# aqicluster_easyeda.net
KiCad netlist of a schematic drawn in EasyEDA
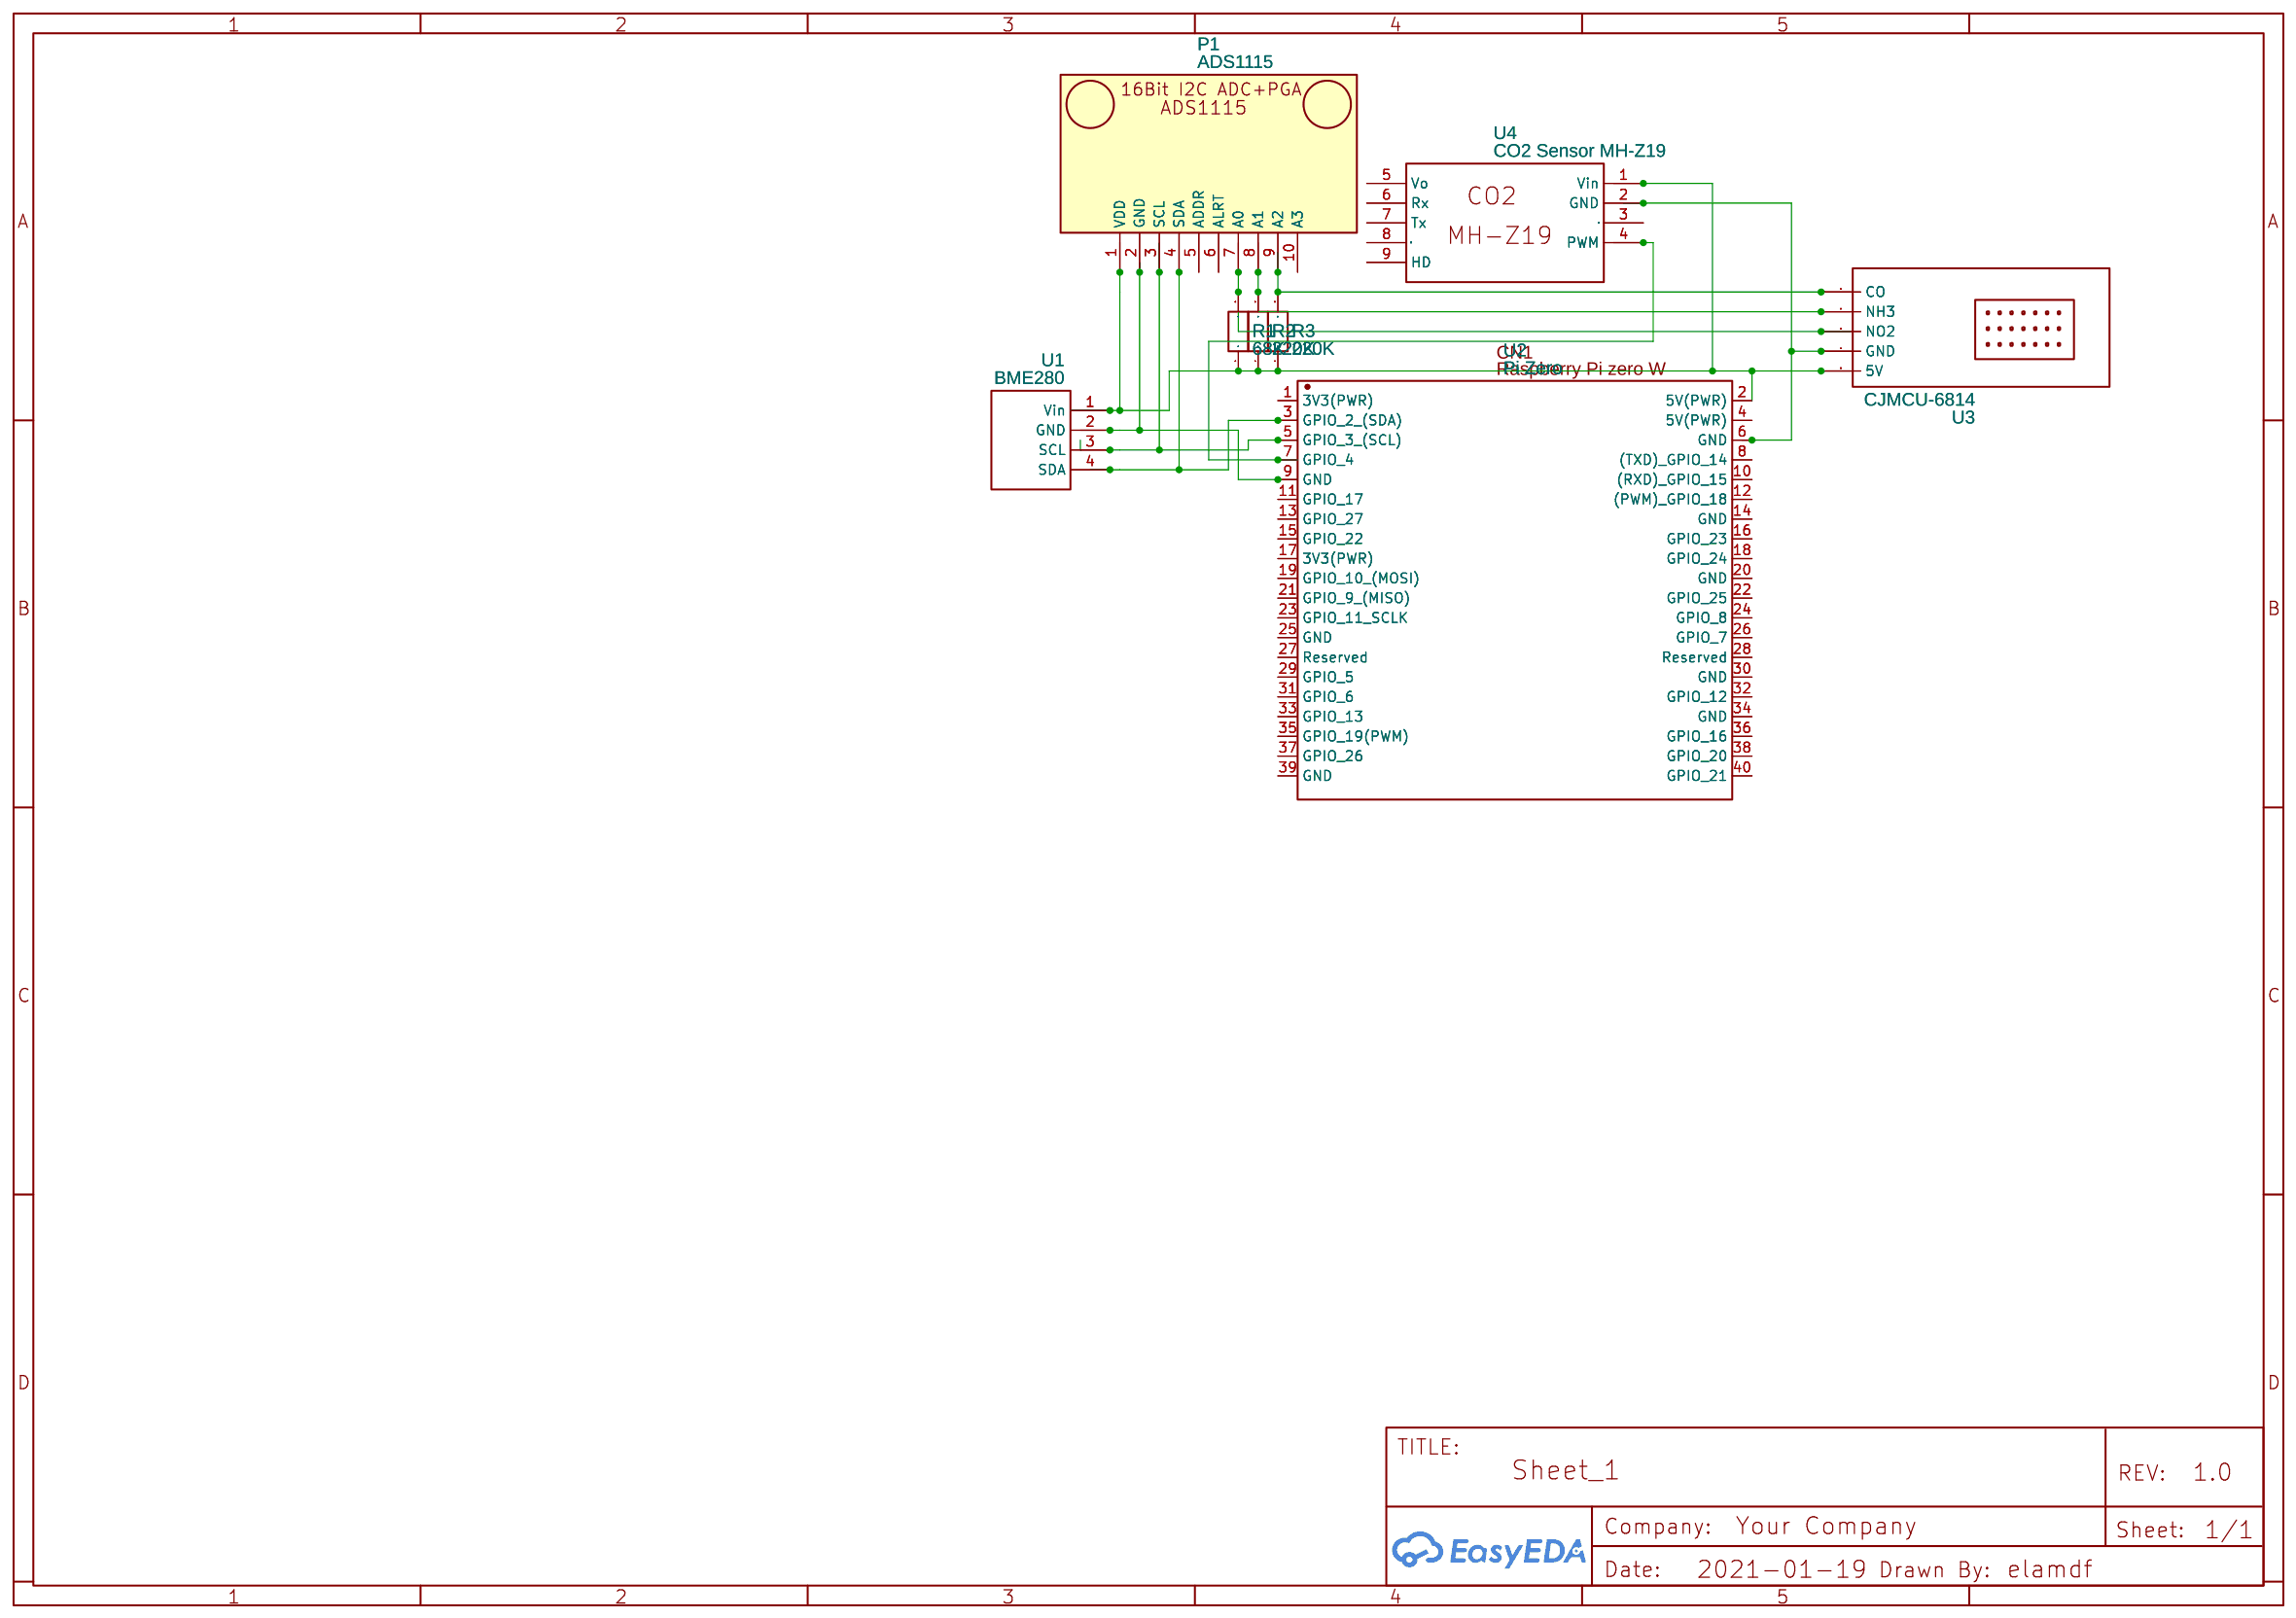
[diagram p0: schematic sheet]

(export (version "E")
  (design (tool "Eeschema 10.0.6"))
  (components
    (comp (ref "P1") (value "ADS1115") (libsource (lib "") (part "ADS1115")))
    (comp (ref "R1") (value "68K") (libsource (lib "") (part "68K")))
    (comp (ref "R2") (value "220K") (libsource (lib "") (part "220K")))
    (comp (ref "R3") (value "220K") (libsource (lib "") (part "220K")))
    (comp (ref "U1") (value "BME280") (libsource (lib "") (part "BME280")))
    (comp (ref "U2") (value "Pi Zero") (libsource (lib "") (part "Pi Zero")))
    (comp (ref "U3")
      (value "CJMCU-6814")
      (fields
        (field (name "BOM_Manufacturer Part") "CJMCU")
        (field (name "BOM_Supplier Part") "https://pt.aliexpress.com/item/32762216430.html")
      )
      (libsource (lib "") (part "CJMCU-6814"))
    )
    (comp (ref "U4") (value "CO2 Sensor MH-Z19") (libsource (lib "") (part "CO2 Sensor MH-Z19")))
  )
  (nets
    (net (code "1") (name "Net-(P1-A0)") (class "Default")
      (node (ref "P1") (pin "7") (pinfunction "A0_7") (pintype "unspecified"))
      (node (ref "R1") (pin "2") (pinfunction "2_2") (pintype "unspecified"))
      (node (ref "U3") (pin "3") (pinfunction "NO2_3") (pintype "unspecified"))
    )
    (net (code "2") (name "Net-(P1-A1)") (class "Default")
      (node (ref "P1") (pin "8") (pinfunction "A1_8") (pintype "unspecified"))
      (node (ref "R2") (pin "2") (pinfunction "2_2") (pintype "unspecified"))
      (node (ref "U3") (pin "2") (pinfunction "NH3_2") (pintype "unspecified"))
    )
    (net (code "3") (name "Net-(P1-A2)") (class "Default")
      (node (ref "P1") (pin "9") (pinfunction "A2_9") (pintype "unspecified"))
      (node (ref "R3") (pin "2") (pinfunction "2_2") (pintype "unspecified"))
      (node (ref "U3") (pin "1") (pinfunction "CO_1") (pintype "unspecified"))
    )
    (net (code "4") (name "Net-(P1-GND)") (class "Default")
      (node (ref "P1") (pin "2") (pinfunction "GND_2") (pintype "passive"))
      (node (ref "U1") (pin "2") (pinfunction "GND_2") (pintype "unspecified"))
      (node (ref "U2") (pin "9") (pinfunction "GND_9") (pintype "passive"))
    )
    (net (code "5") (name "Net-(P1-SCL)") (class "Default")
      (node (ref "P1") (pin "3") (pinfunction "SCL_3") (pintype "bidirectional"))
      (node (ref "U1") (pin "3") (pinfunction "SCL_3") (pintype "unspecified"))
      (node (ref "U2") (pin "5") (pinfunction "GPIO_3_(SCL)_5") (pintype "bidirectional"))
    )
    (net (code "6") (name "Net-(P1-SDA)") (class "Default")
      (node (ref "P1") (pin "4") (pinfunction "SDA_4") (pintype "bidirectional"))
      (node (ref "U1") (pin "4") (pinfunction "SDA_4") (pintype "unspecified"))
      (node (ref "U2") (pin "3") (pinfunction "GPIO_2_(SDA)_3") (pintype "bidirectional"))
    )
    (net (code "7") (name "Net-(P1-VDD)") (class "Default")
      (node (ref "P1") (pin "1") (pinfunction "VDD_1") (pintype "output"))
      (node (ref "R1") (pin "1") (pinfunction "1_1") (pintype "unspecified"))
      (node (ref "R2") (pin "1") (pinfunction "1_1") (pintype "unspecified"))
      (node (ref "R3") (pin "1") (pinfunction "1_1") (pintype "unspecified"))
      (node (ref "U1") (pin "1") (pinfunction "Vin_1") (pintype "unspecified"))
      (node (ref "U2") (pin "2") (pinfunction "5V(PWR)_2") (pintype "passive"))
      (node (ref "U3") (pin "5") (pinfunction "5V_5") (pintype "unspecified"))
      (node (ref "U4") (pin "1") (pinfunction "Vin_1") (pintype "unspecified"))
    )
    (net (code "8") (name "Net-(U2-GPIO_4)") (class "Default")
      (node (ref "U2") (pin "7") (pinfunction "GPIO_4_7") (pintype "bidirectional"))
      (node (ref "U4") (pin "4") (pinfunction "PWM_4") (pintype "unspecified"))
    )
    (net (code "9") (name "Net-(U3-GND)") (class "Default")
      (node (ref "U2") (pin "6") (pinfunction "GND_6") (pintype "passive"))
      (node (ref "U3") (pin "4") (pinfunction "GND_4") (pintype "unspecified"))
      (node (ref "U4") (pin "2") (pinfunction "GND_2") (pintype "unspecified"))
    )
    (net (code "10") (name "unconnected-(P1-A3-Pad10)") (class "Default")
      (node (ref "P1") (pin "10") (pinfunction "A3_10") (pintype "unspecified"))
    )
    (net (code "11") (name "unconnected-(P1-ADDR-Pad5)") (class "Default")
      (node (ref "P1") (pin "5") (pinfunction "ADDR_5") (pintype "passive"))
    )
    (net (code "12") (name "unconnected-(P1-ALRT-Pad6)") (class "Default")
      (node (ref "P1") (pin "6") (pinfunction "ALRT_6") (pintype "passive"))
    )
    (net (code "13") (name "unconnected-(U2-(PWM)_GPIO_18-Pad12)") (class "Default")
      (node (ref "U2") (pin "12") (pinfunction "(PWM)_GPIO_18_12") (pintype "bidirectional"))
    )
    (net (code "14") (name "unconnected-(U2-(RXD)_GPIO_15-Pad10)") (class "Default")
      (node (ref "U2") (pin "10") (pinfunction "(RXD)_GPIO_15_10") (pintype "bidirectional"))
    )
    (net (code "15") (name "unconnected-(U2-(TXD)_GPIO_14-Pad8)") (class "Default")
      (node (ref "U2") (pin "8") (pinfunction "(TXD)_GPIO_14_8") (pintype "passive"))
    )
    (net (code "16") (name "unconnected-(U2-3V3(PWR)-Pad1)") (class "Default")
      (node (ref "U2") (pin "1") (pinfunction "3V3(PWR)_1") (pintype "passive"))
    )
    (net (code "17") (name "unconnected-(U2-3V3(PWR)-Pad17)") (class "Default")
      (node (ref "U2") (pin "17") (pinfunction "3V3(PWR)_17") (pintype "passive"))
    )
    (net (code "18") (name "unconnected-(U2-5V(PWR)-Pad4)") (class "Default")
      (node (ref "U2") (pin "4") (pinfunction "5V(PWR)_4") (pintype "passive"))
    )
    (net (code "19") (name "unconnected-(U2-GND-Pad14)") (class "Default")
      (node (ref "U2") (pin "14") (pinfunction "GND_14") (pintype "passive"))
    )
    (net (code "20") (name "unconnected-(U2-GND-Pad20)") (class "Default")
      (node (ref "U2") (pin "20") (pinfunction "GND_20") (pintype "passive"))
    )
    (net (code "21") (name "unconnected-(U2-GND-Pad25)") (class "Default")
      (node (ref "U2") (pin "25") (pinfunction "GND_25") (pintype "passive"))
    )
    (net (code "22") (name "unconnected-(U2-GND-Pad30)") (class "Default")
      (node (ref "U2") (pin "30") (pinfunction "GND_30") (pintype "passive"))
    )
    (net (code "23") (name "unconnected-(U2-GND-Pad34)") (class "Default")
      (node (ref "U2") (pin "34") (pinfunction "GND_34") (pintype "passive"))
    )
    (net (code "24") (name "unconnected-(U2-GND-Pad39)") (class "Default")
      (node (ref "U2") (pin "39") (pinfunction "GND_39") (pintype "passive"))
    )
    (net (code "25") (name "unconnected-(U2-GPIO_5-Pad29)") (class "Default")
      (node (ref "U2") (pin "29") (pinfunction "GPIO_5_29") (pintype "bidirectional"))
    )
    (net (code "26") (name "unconnected-(U2-GPIO_6-Pad31)") (class "Default")
      (node (ref "U2") (pin "31") (pinfunction "GPIO_6_31") (pintype "bidirectional"))
    )
    (net (code "27") (name "unconnected-(U2-GPIO_7-Pad26)") (class "Default")
      (node (ref "U2") (pin "26") (pinfunction "GPIO_7_26") (pintype "bidirectional"))
    )
    (net (code "28") (name "unconnected-(U2-GPIO_8-Pad24)") (class "Default")
      (node (ref "U2") (pin "24") (pinfunction "GPIO_8_24") (pintype "bidirectional"))
    )
    (net (code "29") (name "unconnected-(U2-GPIO_9_(MISO)-Pad21)") (class "Default")
      (node (ref "U2") (pin "21") (pinfunction "GPIO_9_(MISO)_21") (pintype "bidirectional"))
    )
    (net (code "30") (name "unconnected-(U2-GPIO_10_(MOSI)-Pad19)") (class "Default")
      (node (ref "U2") (pin "19") (pinfunction "GPIO_10_(MOSI)_19") (pintype "bidirectional"))
    )
    (net (code "31") (name "unconnected-(U2-GPIO_11_SCLK-Pad23)") (class "Default")
      (node (ref "U2") (pin "23") (pinfunction "GPIO_11_SCLK_23") (pintype "bidirectional"))
    )
    (net (code "32") (name "unconnected-(U2-GPIO_12-Pad32)") (class "Default")
      (node (ref "U2") (pin "32") (pinfunction "GPIO_12_32") (pintype "bidirectional"))
    )
    (net (code "33") (name "unconnected-(U2-GPIO_13-Pad33)") (class "Default")
      (node (ref "U2") (pin "33") (pinfunction "GPIO_13_33") (pintype "bidirectional"))
    )
    (net (code "34") (name "unconnected-(U2-GPIO_16-Pad36)") (class "Default")
      (node (ref "U2") (pin "36") (pinfunction "GPIO_16_36") (pintype "bidirectional"))
    )
    (net (code "35") (name "unconnected-(U2-GPIO_17-Pad11)") (class "Default")
      (node (ref "U2") (pin "11") (pinfunction "GPIO_17_11") (pintype "bidirectional"))
    )
    (net (code "36") (name "unconnected-(U2-GPIO_19(PWM)-Pad35)") (class "Default")
      (node (ref "U2") (pin "35") (pinfunction "GPIO_19(PWM)_35") (pintype "bidirectional"))
    )
    (net (code "37") (name "unconnected-(U2-GPIO_20-Pad38)") (class "Default")
      (node (ref "U2") (pin "38") (pinfunction "GPIO_20_38") (pintype "bidirectional"))
    )
    (net (code "38") (name "unconnected-(U2-GPIO_21-Pad40)") (class "Default")
      (node (ref "U2") (pin "40") (pinfunction "GPIO_21_40") (pintype "bidirectional"))
    )
    (net (code "39") (name "unconnected-(U2-GPIO_22-Pad15)") (class "Default")
      (node (ref "U2") (pin "15") (pinfunction "GPIO_22_15") (pintype "output"))
    )
    (net (code "40") (name "unconnected-(U2-GPIO_23-Pad16)") (class "Default")
      (node (ref "U2") (pin "16") (pinfunction "GPIO_23_16") (pintype "bidirectional"))
    )
    (net (code "41") (name "unconnected-(U2-GPIO_24-Pad18)") (class "Default")
      (node (ref "U2") (pin "18") (pinfunction "GPIO_24_18") (pintype "bidirectional"))
    )
    (net (code "42") (name "unconnected-(U2-GPIO_25-Pad22)") (class "Default")
      (node (ref "U2") (pin "22") (pinfunction "GPIO_25_22") (pintype "bidirectional"))
    )
    (net (code "43") (name "unconnected-(U2-GPIO_26-Pad37)") (class "Default")
      (node (ref "U2") (pin "37") (pinfunction "GPIO_26_37") (pintype "bidirectional"))
    )
    (net (code "44") (name "unconnected-(U2-GPIO_27-Pad13)") (class "Default")
      (node (ref "U2") (pin "13") (pinfunction "GPIO_27_13") (pintype "bidirectional"))
    )
    (net (code "45") (name "unconnected-(U2-Reserved-Pad27)") (class "Default")
      (node (ref "U2") (pin "27") (pinfunction "Reserved_27") (pintype "unspecified"))
    )
    (net (code "46") (name "unconnected-(U2-Reserved-Pad28)") (class "Default")
      (node (ref "U2") (pin "28") (pinfunction "Reserved_28") (pintype "unspecified"))
    )
    (net (code "47") (name "unconnected-(U4-HD-Pad9)") (class "Default")
      (node (ref "U4") (pin "9") (pinfunction "HD_9") (pintype "unspecified"))
    )
    (net (code "48") (name "unconnected-(U4-Pad3)") (class "Default")
      (node (ref "U4") (pin "3") (pinfunction "3_3") (pintype "unspecified"))
    )
    (net (code "49") (name "unconnected-(U4-Pad8)") (class "Default")
      (node (ref "U4") (pin "8") (pinfunction "8_8") (pintype "unspecified"))
    )
    (net (code "50") (name "unconnected-(U4-Rx-Pad6)") (class "Default")
      (node (ref "U4") (pin "6") (pinfunction "Rx_6") (pintype "unspecified"))
    )
    (net (code "51") (name "unconnected-(U4-Tx-Pad7)") (class "Default")
      (node (ref "U4") (pin "7") (pinfunction "Tx_7") (pintype "unspecified"))
    )
    (net (code "52") (name "unconnected-(U4-Vo-Pad5)") (class "Default")
      (node (ref "U4") (pin "5") (pinfunction "Vo_5") (pintype "unspecified"))
    )
  )
)
